# AS3933.net
KiCad netlist of a schematic drawn in Altium Designer
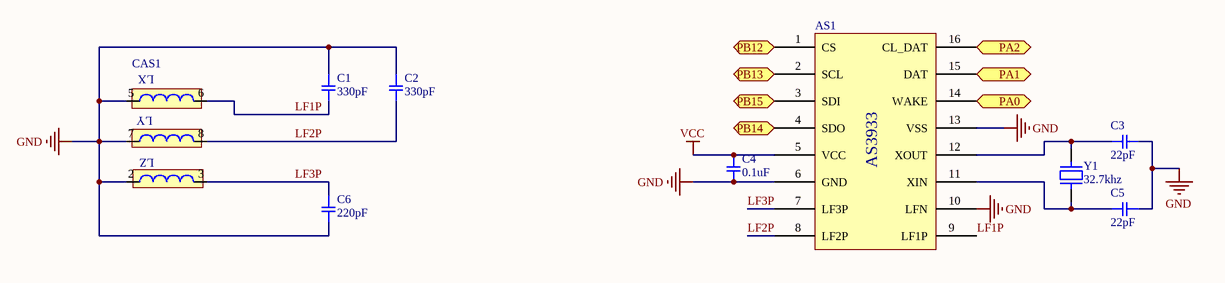
[diagram p0: AS3933.SchDoc]

(export (version "E")
  (design (tool "Eeschema 10.0.6"))
  (components
    (comp (ref "AS1")
      (value "~")
      (footprint "TSOP65P640X110-16N")
      (libsource (lib "AS3933") (part "Component_1"))
    )
    (comp (ref "C1")
      (value "330pF")
      (footprint "SMD-0805C")
      (description "Cap Ceramic 330pF 50V C0G 2%  0805")
      (fields (field (name "PART NUMBER") "CC0805GRNPO9BN331") (field (name "MANUFACTURER") "Yageo"))
      (libsource (lib "capacitor_0805") (part "CC0805GRNPO9BN331"))
    )
    (comp (ref "C2")
      (value "330pF")
      (footprint "SMD-0805C")
      (description "Cap Ceramic 330pF 50V C0G 2%  0805")
      (fields (field (name "PART NUMBER") "CC0805GRNPO9BN331") (field (name "MANUFACTURER") "Yageo"))
      (libsource (lib "capacitor_0805") (part "CC0805GRNPO9BN331"))
    )
    (comp (ref "C3")
      (value "22pF")
      (footprint "SMD-0805C")
      (description "Cap Ceramic 22pF 50V C0G 5%0805")
      (fields
        (field (name "PART NUMBER") "CL21C220JBANNND")
        (field (name "MANUFACTURER") "Samsung Electro-Mechanics")
      )
      (libsource (lib "capacitor_0805") (part "CL21C220JBANNND"))
    )
    (comp (ref "C4")
      (value "0.1uF")
      (footprint "SMD-0805C")
      (description "CAP CER 0.1uF 50V X7T 0805")
      (fields
        (field (name "PART NUMBER") "GC321AD72E103KX01D")
        (field (name "MANUFACTURER") "Samsung Electro-Mechanics")
      )
      (libsource (lib "capacitor_0805") (part "CL21B104JBCNNNC"))
    )
    (comp (ref "C5")
      (value "22pF")
      (footprint "SMD-0805C")
      (description "Cap Ceramic 22pF 50V C0G 5%0805")
      (fields
        (field (name "PART NUMBER") "CL21C220JBANNND")
        (field (name "MANUFACTURER") "Samsung Electro-Mechanics")
      )
      (libsource (lib "capacitor_0805") (part "CL21C220JBANNND"))
    )
    (comp (ref "C6")
      (value "220pF")
      (footprint "SMD-0805C")
      (description "Cap Ceramic 220pF 100V C0G 1% 0805")
      (fields
        (field (name "PART NUMBER") "GCM2165C2A221FA16D")
        (field (name "MANUFACTURER") "Murata Manufacturing")
      )
      (libsource (lib "capacitor_0805") (part "GCM2165C2A221FA16D"))
    )
    (comp (ref "CAS1")
      (value "CAS143-47")
      (footprint "CAS143-47")
      (libsource (lib "CAS143-47") (part "Component_1"))
    )
    (comp (ref "Y1")
      (value "32.7khz")
      (footprint "ABRACON ABS07")
      (description "SMT Crystal")
      (libsource (lib "Tesis") (part "Abracon Crystal ABS07"))
    )
  )
  (nets
    (net (code "1") (name "/LF1P") (class "Default")
      (node (ref "AS1") (pin "9") (pinfunction "LF1P_9") (pintype "passive"))
      (node (ref "C1") (pin "2") (pinfunction "2_2") (pintype "passive"))
      (node (ref "CAS1") (pin "6") (pinfunction "6_6") (pintype "passive"))
    )
    (net (code "2") (name "/LF2P") (class "Default")
      (node (ref "AS1") (pin "8") (pinfunction "LF2P_8") (pintype "passive"))
      (node (ref "C2") (pin "2") (pinfunction "2_2") (pintype "passive"))
      (node (ref "CAS1") (pin "8") (pinfunction "8_8") (pintype "passive"))
    )
    (net (code "3") (name "/LF3P") (class "Default")
      (node (ref "AS1") (pin "7") (pinfunction "LF3P_7") (pintype "passive"))
      (node (ref "C6") (pin "1") (pinfunction "1_1") (pintype "passive"))
      (node (ref "CAS1") (pin "3") (pinfunction "3_3") (pintype "passive"))
    )
    (net (code "4") (name "/PA0") (class "Default")
      (node (ref "AS1") (pin "14") (pinfunction "WAKE_14") (pintype "passive"))
    )
    (net (code "5") (name "/PA1") (class "Default")
      (node (ref "AS1") (pin "15") (pinfunction "DAT_15") (pintype "passive"))
    )
    (net (code "6") (name "/PA2") (class "Default")
      (node (ref "AS1") (pin "16") (pinfunction "CL_DAT_16") (pintype "passive"))
    )
    (net (code "7") (name "/PB12") (class "Default")
      (node (ref "AS1") (pin "1") (pinfunction "CS_1") (pintype "passive"))
    )
    (net (code "8") (name "/PB13") (class "Default")
      (node (ref "AS1") (pin "2") (pinfunction "SCL_2") (pintype "passive"))
    )
    (net (code "9") (name "/PB14") (class "Default")
      (node (ref "AS1") (pin "4") (pinfunction "SDO_4") (pintype "passive"))
    )
    (net (code "10") (name "/PB15") (class "Default")
      (node (ref "AS1") (pin "3") (pinfunction "SDI_3") (pintype "passive"))
    )
    (net (code "11") (name "GND") (class "Default")
      (node (ref "AS1") (pin "10") (pinfunction "LFN_10") (pintype "passive"))
      (node (ref "AS1") (pin "13") (pinfunction "VSS_13") (pintype "passive"))
      (node (ref "AS1") (pin "6") (pinfunction "GND_6") (pintype "passive"))
      (node (ref "C1") (pin "1") (pinfunction "1_1") (pintype "passive"))
      (node (ref "C2") (pin "1") (pinfunction "1_1") (pintype "passive"))
      (node (ref "C3") (pin "1") (pinfunction "1_1") (pintype "passive"))
      (node (ref "C4") (pin "2") (pinfunction "2_2") (pintype "passive"))
      (node (ref "C5") (pin "1") (pinfunction "1_1") (pintype "passive"))
      (node (ref "C6") (pin "2") (pinfunction "2_2") (pintype "passive"))
      (node (ref "CAS1") (pin "2") (pinfunction "2_2") (pintype "passive"))
      (node (ref "CAS1") (pin "5") (pinfunction "5_5") (pintype "passive"))
      (node (ref "CAS1") (pin "7") (pinfunction "7_7") (pintype "passive"))
    )
    (net (code "12") (name "Net-(AS1-XIN)") (class "Default")
      (node (ref "AS1") (pin "11") (pinfunction "XIN_11") (pintype "passive"))
      (node (ref "C5") (pin "2") (pinfunction "2_2") (pintype "passive"))
      (node (ref "Y1") (pin "1") (pinfunction "1_1") (pintype "passive"))
    )
    (net (code "13") (name "Net-(AS1-XOUT)") (class "Default")
      (node (ref "AS1") (pin "12") (pinfunction "XOUT_12") (pintype "passive"))
      (node (ref "C3") (pin "2") (pinfunction "2_2") (pintype "passive"))
      (node (ref "Y1") (pin "2") (pinfunction "2_2") (pintype "passive"))
    )
    (net (code "14") (name "VCC") (class "Default")
      (node (ref "AS1") (pin "5") (pinfunction "VCC_5") (pintype "passive"))
      (node (ref "C4") (pin "1") (pinfunction "1_1") (pintype "passive"))
    )
  )
)
